# controller6.net
KiCad netlist of a schematic drawn in EAGLE
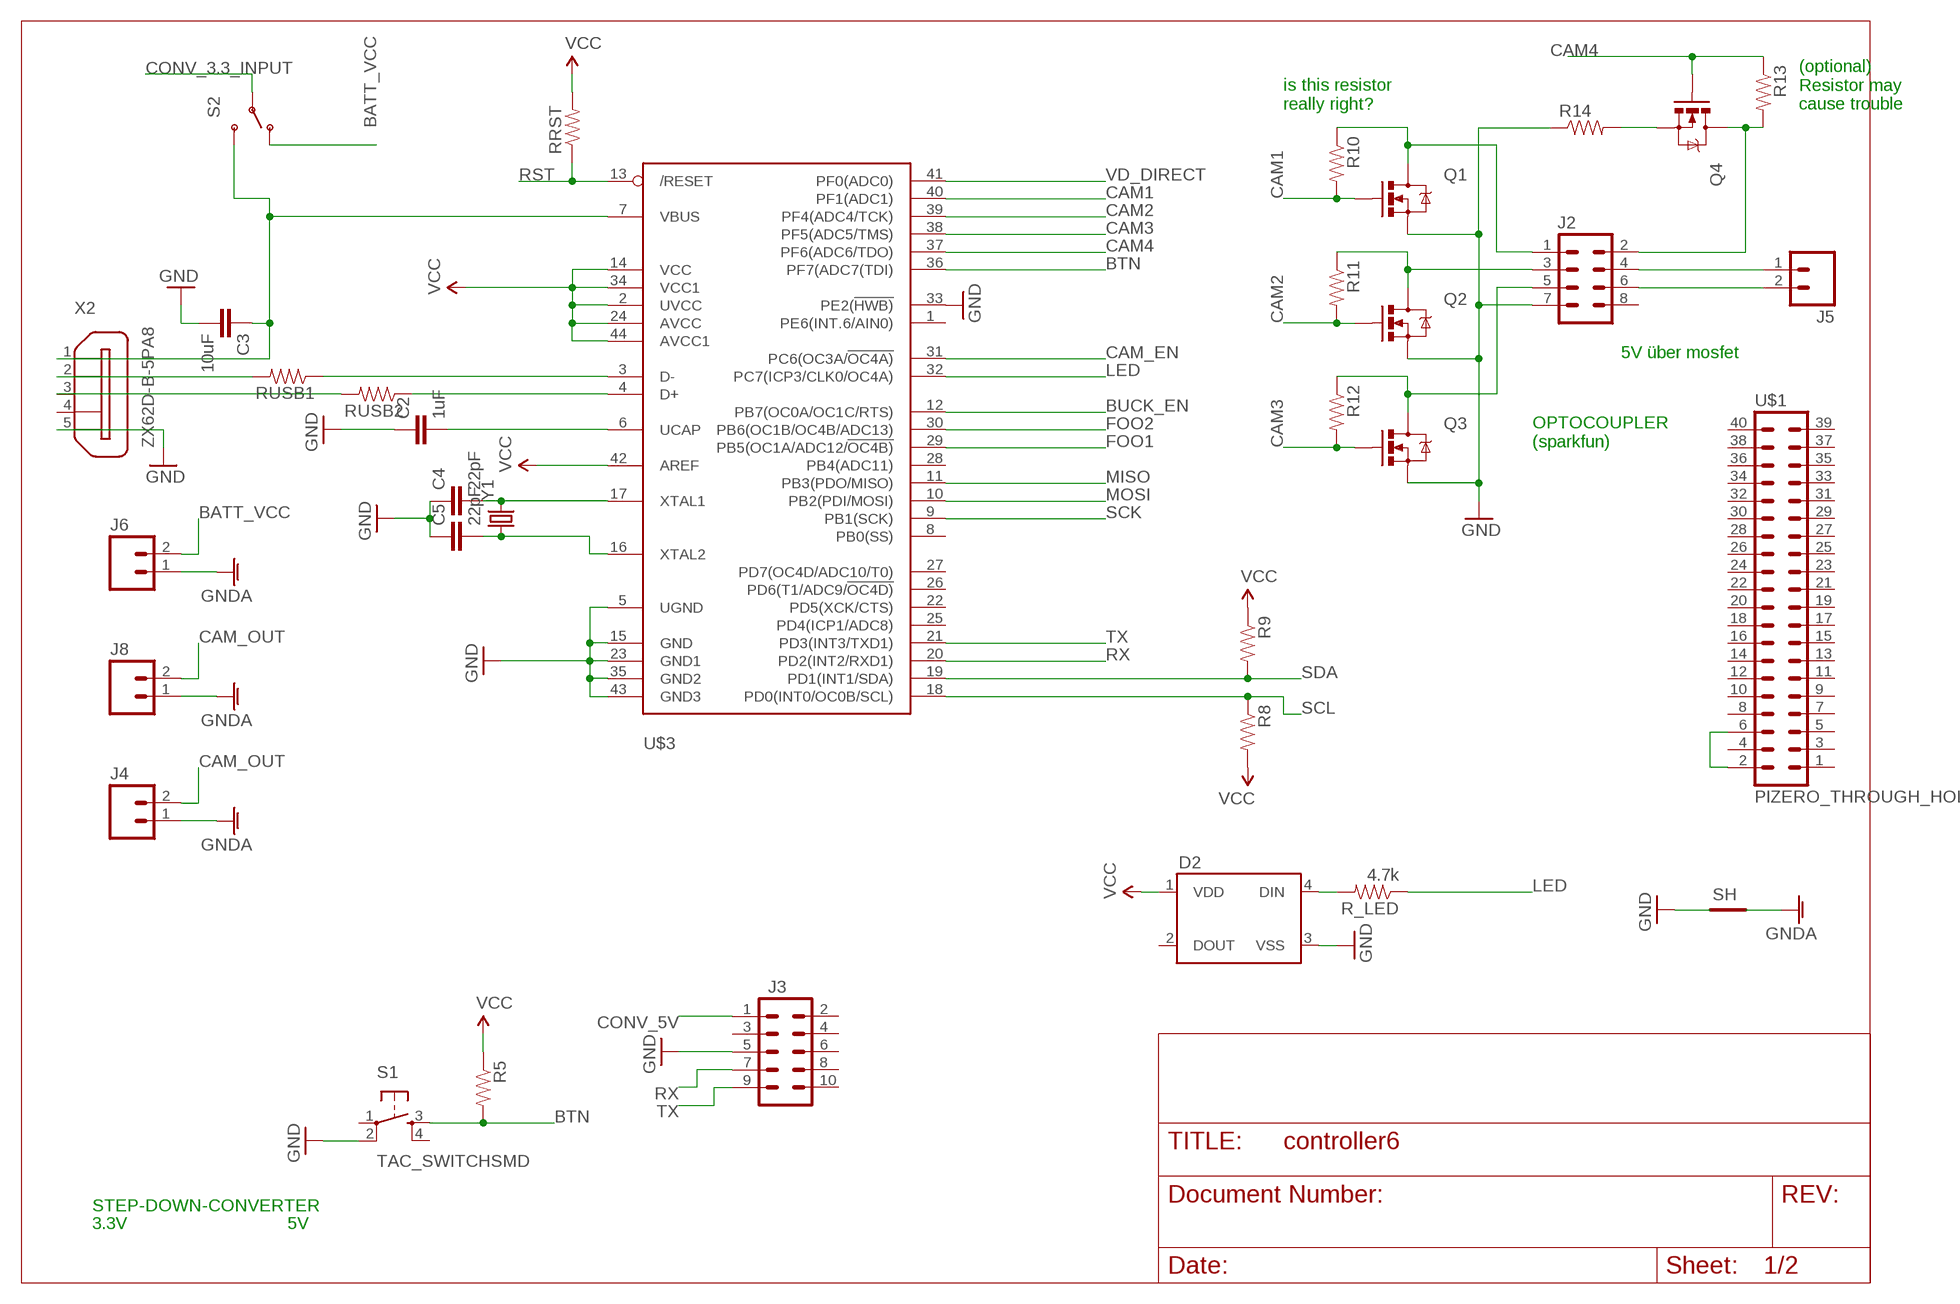
[diagram p0: schematic, sheet 1]
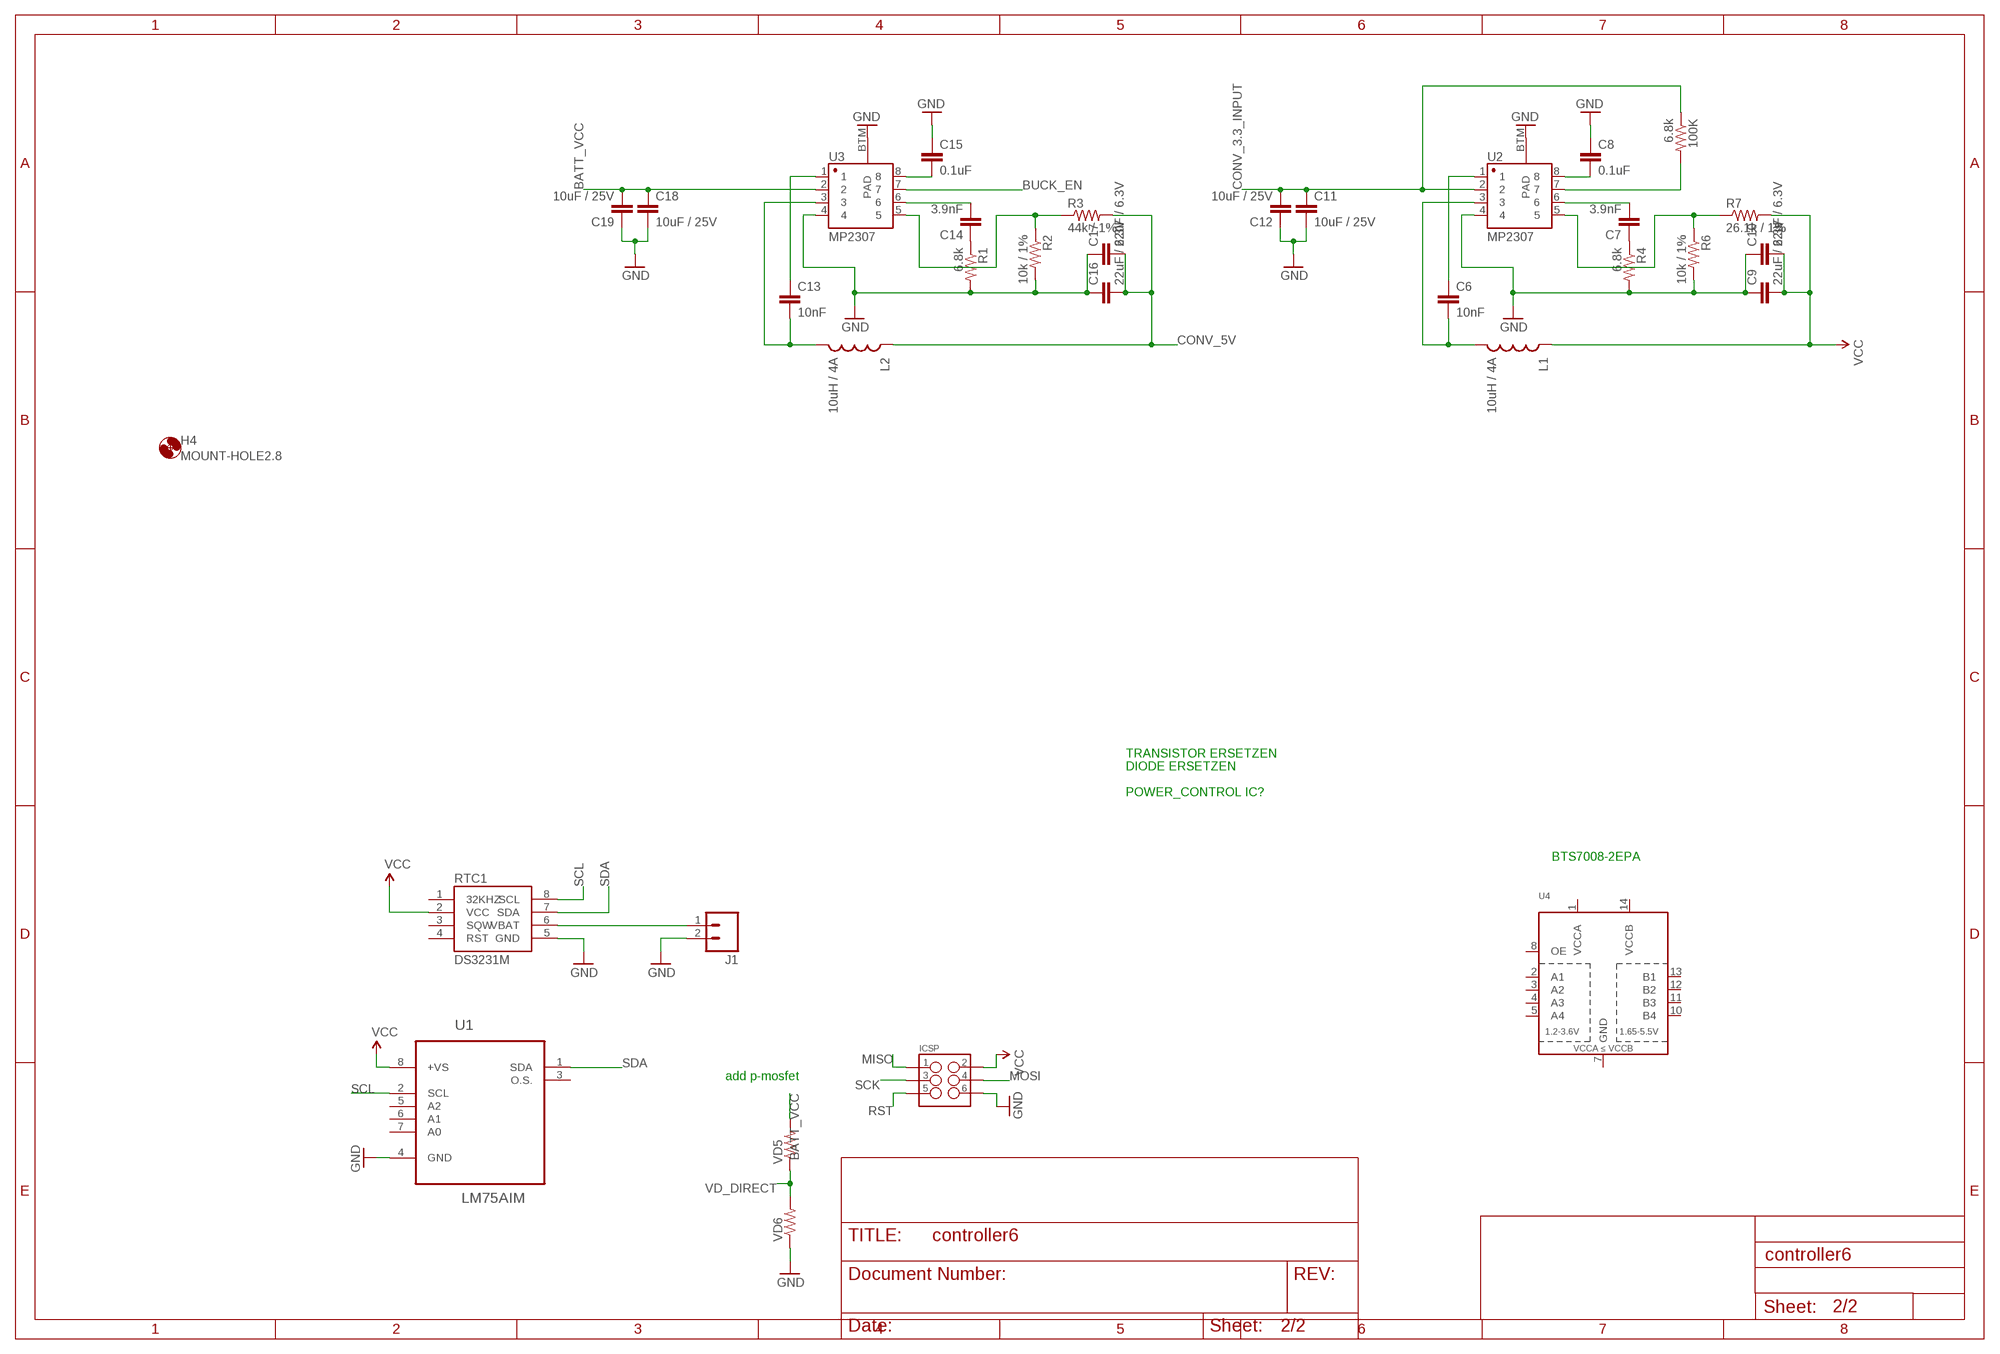
[diagram p1: schematic, sheet 2]

(export (version "E")
  (design (tool "Eeschema 10.0.6"))
  (components
    (comp (ref "100K")
      (value "6.8k")
      (footprint "eagle-import:0805")
      (libsource (lib "eagle-import") (part "SparkFun-Resistors_RESISTOR0805-RES"))
    )
    (comp (ref "C6")
      (value "10nF")
      (footprint "eagle-import:1206")
      (libsource (lib "eagle-import") (part "CAP1206"))
    )
    (comp (ref "C7")
      (value "3.9nF")
      (footprint "eagle-import:0805")
      (libsource (lib "eagle-import") (part "CAP0805"))
    )
    (comp (ref "C8")
      (value "0.1uF")
      (footprint "eagle-import:0805")
      (libsource (lib "eagle-import") (part "CAP0805"))
    )
    (comp (ref "C9")
      (value "22uF / 6.3V")
      (footprint "eagle-import:1206")
      (libsource (lib "eagle-import") (part "CAP1206"))
    )
    (comp (ref "C10")
      (value "22uF / 6.3V")
      (footprint "eagle-import:1206")
      (libsource (lib "eagle-import") (part "CAP1206"))
    )
    (comp (ref "C11")
      (value "10uF / 25V")
      (footprint "eagle-import:1206")
      (libsource (lib "eagle-import") (part "CAP1206"))
    )
    (comp (ref "C12")
      (value "10uF / 25V")
      (footprint "eagle-import:1206")
      (libsource (lib "eagle-import") (part "CAP1206"))
    )
    (comp (ref "C13")
      (value "10nF")
      (footprint "eagle-import:1206")
      (libsource (lib "eagle-import") (part "CAP1206"))
    )
    (comp (ref "C14")
      (value "3.9nF")
      (footprint "eagle-import:0805")
      (libsource (lib "eagle-import") (part "CAP0805"))
    )
    (comp (ref "C15")
      (value "0.1uF")
      (footprint "eagle-import:0805")
      (libsource (lib "eagle-import") (part "CAP0805"))
    )
    (comp (ref "C16")
      (value "22uF / 6.3V")
      (footprint "eagle-import:1206")
      (libsource (lib "eagle-import") (part "CAP1206"))
    )
    (comp (ref "C17")
      (value "22uF / 6.3V")
      (footprint "eagle-import:1206")
      (libsource (lib "eagle-import") (part "CAP1206"))
    )
    (comp (ref "C18")
      (value "10uF / 25V")
      (footprint "eagle-import:1206")
      (libsource (lib "eagle-import") (part "CAP1206"))
    )
    (comp (ref "C19")
      (value "10uF / 25V")
      (footprint "eagle-import:1206")
      (libsource (lib "eagle-import") (part "CAP1206"))
    )
    (comp (ref "H4")
      (value "MOUNT-HOLE2.8")
      (footprint "eagle-import:2,8")
      (libsource (lib "eagle-import") (part "MOUNT-HOLE2.8"))
    )
    (comp (ref "ICSP")
      (value "M03X2FEMALE")
      (footprint "eagle-import:2X3")
      (libsource (lib "eagle-import") (part "M03X2FEMALE"))
    )
    (comp (ref "J1")
      (value "M02LOCK_LONGPADS")
      (footprint "eagle-import:1X02_LOCK_LONGPADS")
      (libsource (lib "eagle-import") (part "M02LOCK_LONGPADS"))
    )
    (comp (ref "L1")
      (value "10uH / 4A")
      (footprint "eagle-import:SDR0403")
      (libsource (lib "eagle-import") (part "INDUCTORSDR0403-560KL"))
    )
    (comp (ref "L2")
      (value "10uH / 4A")
      (footprint "eagle-import:SDR0403")
      (libsource (lib "eagle-import") (part "INDUCTORSDR0403-560KL"))
    )
    (comp (ref "R1")
      (value "6.8k")
      (footprint "eagle-import:0805")
      (libsource (lib "eagle-import") (part "SparkFun-Resistors_RESISTOR0805-RES"))
    )
    (comp (ref "R2")
      (value "10k / 1%")
      (footprint "eagle-import:0805")
      (libsource (lib "eagle-import") (part "SparkFun-Resistors_RESISTOR0805-RES"))
    )
    (comp (ref "R3")
      (value "44k / 1%")
      (footprint "eagle-import:0805")
      (libsource (lib "eagle-import") (part "SparkFun-Resistors_RESISTOR0805-RES"))
    )
    (comp (ref "R4")
      (value "6.8k")
      (footprint "eagle-import:0805")
      (libsource (lib "eagle-import") (part "SparkFun-Resistors_RESISTOR0805-RES"))
    )
    (comp (ref "R6")
      (value "10k / 1%")
      (footprint "eagle-import:0805")
      (libsource (lib "eagle-import") (part "SparkFun-Resistors_RESISTOR0805-RES"))
    )
    (comp (ref "R7")
      (value "26.1k / 1%")
      (footprint "eagle-import:0805")
      (libsource (lib "eagle-import") (part "SparkFun-Resistors_RESISTOR0805-RES"))
    )
    (comp (ref "RTC1")
      (value "DS3231M")
      (footprint "eagle-import:SOIC8")
      (libsource (lib "eagle-import") (part "DS3231M"))
    )
    (comp (ref "U1")
      (value "LM75AIM")
      (footprint "eagle-import:SOIC127P620X175-8N")
      (libsource (lib "eagle-import") (part "LM75AIM"))
    )
    (comp (ref "U2")
      (value "MP2307")
      (footprint "eagle-import:SO08")
      (libsource (lib "eagle-import") (part "GENERIC-SOIC8MSGEQ7N-FILTER"))
    )
    (comp (ref "U3")
      (value "MP2307")
      (footprint "eagle-import:SO08")
      (libsource (lib "eagle-import") (part "GENERIC-SOIC8MSGEQ7N-FILTER"))
    )
    (comp (ref "U4")
      (value "TXB0104PWRSOIC14")
      (footprint "eagle-import:SO14")
      (libsource (lib "eagle-import") (part "TXB0104PWRSOIC14"))
    )
    (comp (ref "VD5")
      (value "RESISTOR1206")
      (footprint "eagle-import:1206")
      (libsource (lib "eagle-import") (part "RESISTOR1206"))
    )
    (comp (ref "VD6")
      (value "RESISTOR1206")
      (footprint "eagle-import:1206")
      (libsource (lib "eagle-import") (part "RESISTOR1206"))
    )
    (comp (ref "C2")
      (value "1uF")
      (footprint "eagle-import:1206")
      (libsource (lib "eagle-import") (part "CAP1206"))
    )
    (comp (ref "C3")
      (value "10uF")
      (footprint "eagle-import:0805")
      (libsource (lib "eagle-import") (part "SparkFun-Passives_CAP0805"))
    )
    (comp (ref "C4")
      (value "22pF")
      (footprint "eagle-import:0805")
      (libsource (lib "eagle-import") (part "SparkFun-Passives_CAP0805"))
    )
    (comp (ref "C5")
      (value "22pF")
      (footprint "eagle-import:0805")
      (libsource (lib "eagle-import") (part "SparkFun-Passives_CAP0805"))
    )
    (comp (ref "D2")
      (value "WS2812B")
      (footprint "eagle-import:WS2812B")
      (libsource (lib "eagle-import") (part "WS2812B"))
    )
    (comp (ref "J2")
      (value "M04X2")
      (footprint "eagle-import:2X4")
      (libsource (lib "eagle-import") (part "M04X2"))
    )
    (comp (ref "J3")
      (value "M05X2NO_SILK")
      (footprint "eagle-import:2X5_NOSILK")
      (libsource (lib "eagle-import") (part "M05X2NO_SILK"))
    )
    (comp (ref "J4")
      (value "M02LOCK")
      (footprint "eagle-import:1X02_LOCK")
      (libsource (lib "eagle-import") (part "M02LOCK"))
    )
    (comp (ref "J5")
      (value "M02PTH")
      (footprint "eagle-import:1X02")
      (libsource (lib "eagle-import") (part "M02PTH"))
    )
    (comp (ref "J6")
      (value "M02LOCK")
      (footprint "eagle-import:1X02_LOCK")
      (libsource (lib "eagle-import") (part "M02LOCK"))
    )
    (comp (ref "J8")
      (value "M02LOCK")
      (footprint "eagle-import:1X02_LOCK")
      (libsource (lib "eagle-import") (part "M02LOCK"))
    )
    (comp (ref "Q1")
      (value "MOSFET-NCHANNELBSS138")
      (footprint "eagle-import:SOT23-3")
      (libsource (lib "eagle-import") (part "MOSFET-NCHANNELBSS138"))
    )
    (comp (ref "Q2")
      (value "MOSFET-NCHANNELBSS138")
      (footprint "eagle-import:SOT23-3")
      (libsource (lib "eagle-import") (part "MOSFET-NCHANNELBSS138"))
    )
    (comp (ref "Q3")
      (value "MOSFET-NCHANNELBSS138")
      (footprint "eagle-import:SOT23-3")
      (libsource (lib "eagle-import") (part "MOSFET-NCHANNELBSS138"))
    )
    (comp (ref "Q4")
      (value "MOSFET-NCHANNELBSS138")
      (footprint "eagle-import:SOT23-3")
      (libsource (lib "eagle-import") (part "MOSFET-NCHANNELBSS138"))
    )
    (comp (ref "R5")
      (value "RESISTOR0805-RES")
      (footprint "eagle-import:0805")
      (libsource (lib "eagle-import") (part "RESISTOR0805-RES"))
    )
    (comp (ref "R8")
      (value "RESISTOR0805-RES")
      (footprint "eagle-import:0805")
      (libsource (lib "eagle-import") (part "RESISTOR0805-RES"))
    )
    (comp (ref "R9")
      (value "RESISTOR0805-RES")
      (footprint "eagle-import:0805")
      (libsource (lib "eagle-import") (part "RESISTOR0805-RES"))
    )
    (comp (ref "R10")
      (value "RESISTOR0805-RES")
      (footprint "eagle-import:0805")
      (libsource (lib "eagle-import") (part "RESISTOR0805-RES"))
    )
    (comp (ref "R11")
      (value "RESISTOR0805-RES")
      (footprint "eagle-import:0805")
      (libsource (lib "eagle-import") (part "RESISTOR0805-RES"))
    )
    (comp (ref "R12")
      (value "RESISTOR0805-RES")
      (footprint "eagle-import:0805")
      (libsource (lib "eagle-import") (part "RESISTOR0805-RES"))
    )
    (comp (ref "R13")
      (value "RESISTOR0805-RES")
      (footprint "eagle-import:0805")
      (libsource (lib "eagle-import") (part "RESISTOR0805-RES"))
    )
    (comp (ref "R14")
      (value "RESISTOR0805-RES")
      (footprint "eagle-import:0805")
      (libsource (lib "eagle-import") (part "RESISTOR0805-RES"))
    )
    (comp (ref "RRST")
      (value "RESISTOR0805-RES")
      (footprint "eagle-import:0805")
      (libsource (lib "eagle-import") (part "RESISTOR0805-RES"))
    )
    (comp (ref "RUSB1")
      (value "RESISTOR0805-RES")
      (footprint "eagle-import:0805")
      (libsource (lib "eagle-import") (part "RESISTOR0805-RES"))
    )
    (comp (ref "RUSB2")
      (value "RESISTOR0805-RES")
      (footprint "eagle-import:0805")
      (libsource (lib "eagle-import") (part "RESISTOR0805-RES"))
    )
    (comp (ref "R_LED")
      (value "4.7k")
      (footprint "eagle-import:0805")
      (libsource (lib "eagle-import") (part "SparkFun-Resistors_RESISTOR0805-RES"))
    )
    (comp (ref "S1")
      (value "TAC_SWITCHSMD")
      (footprint "eagle-import:TACTILE-SWITCH-SMD")
      (libsource (lib "eagle-import") (part "TAC_SWITCHSMD"))
    )
    (comp (ref "S2")
      (value "SWITCH-SPDTPTH_LOCK")
      (footprint "eagle-import:SWITCH-SPDT_LOCK.007S")
      (libsource (lib "eagle-import") (part "SWITCH-SPDTPTH_LOCK"))
    )
    (comp (ref "SH")
      (value "SHORT-HT5")
      (footprint "eagle-import:SHORT_TOP-50")
      (libsource (lib "eagle-import") (part "SHORT-HT5"))
    )
    (comp (ref "U$1")
      (value "PIZERO_THROUGH_HOLE")
      (footprint "eagle-import:PIZERO_THOUGH_HOLE")
      (libsource (lib "eagle-import") (part "PIZERO_THROUGH_HOLE"))
    )
    (comp (ref "U$3")
      (value "ATMEGA32U4-AU")
      (footprint "eagle-import:TQFP44")
      (libsource (lib "eagle-import") (part "ATMEGA32U4-AU"))
    )
    (comp (ref "X2")
      (value "ZX62D-B-5PA8")
      (footprint "eagle-import:ZX62D-B-5PA8")
      (fields (field (name "MF") "Hirose"))
      (libsource (lib "eagle-import") (part "ZX62D-B-5PA8"))
    )
    (comp (ref "Y1")
      (value "CRYSTALCRYSTAL-SMD-5X3-16MHZ")
      (footprint "eagle-import:CRYSTAL-SMD-5X3")
      (libsource (lib "eagle-import") (part "CRYSTALCRYSTAL-SMD-5X3-16MHZ"))
    )
  )
  (nets
    (net (code "1") (name "BATT_VCC") (class "Default")
      (node (ref "C18") (pin "1") (pinfunction "1_1") (pintype "passive"))
      (node (ref "C19") (pin "2") (pinfunction "2_2") (pintype "passive"))
      (node (ref "J6") (pin "2") (pinfunction "2_2") (pintype "passive"))
      (node (ref "S2") (pin "1") (pinfunction "O_1") (pintype "passive"))
      (node (ref "U3") (pin "2") (pinfunction "2_2") (pintype "bidirectional"))
      (node (ref "VD5") (pin "2") (pinfunction "2_2") (pintype "passive"))
    )
    (net (code "2") (name "BTN") (class "Default")
      (node (ref "R5") (pin "2") (pinfunction "2_2") (pintype "passive"))
      (node (ref "S1") (pin "3") (pinfunction "3_3") (pintype "passive"))
      (node (ref "U$3") (pin "36") (pinfunction "PF7(ADC7(TDI)_36") (pintype "bidirectional"))
    )
    (net (code "3") (name "BUCK_EN") (class "Default")
      (node (ref "U$3") (pin "12") (pinfunction "PB7(OC0A/OC1C/RTS)_12") (pintype "bidirectional"))
      (node (ref "U3") (pin "7") (pinfunction "7_7") (pintype "bidirectional"))
    )
    (net (code "4") (name "CAM1") (class "Default")
      (node (ref "Q1") (pin "1") (pinfunction "G_1") (pintype "passive"))
      (node (ref "R10") (pin "2") (pinfunction "2_2") (pintype "passive"))
      (node (ref "U$3") (pin "40") (pinfunction "PF1(ADC1)_40") (pintype "bidirectional"))
    )
    (net (code "5") (name "CAM2") (class "Default")
      (node (ref "Q2") (pin "1") (pinfunction "G_1") (pintype "passive"))
      (node (ref "R11") (pin "2") (pinfunction "2_2") (pintype "passive"))
      (node (ref "U$3") (pin "39") (pinfunction "PF4(ADC4/TCK)_39") (pintype "bidirectional"))
    )
    (net (code "6") (name "CAM3") (class "Default")
      (node (ref "Q3") (pin "1") (pinfunction "G_1") (pintype "passive"))
      (node (ref "R12") (pin "2") (pinfunction "2_2") (pintype "passive"))
      (node (ref "U$3") (pin "38") (pinfunction "PF5(ADC5/TMS)_38") (pintype "bidirectional"))
    )
    (net (code "7") (name "CAM4") (class "Default")
      (node (ref "Q4") (pin "1") (pinfunction "G_1") (pintype "passive"))
      (node (ref "R13") (pin "1") (pinfunction "1_1") (pintype "passive"))
      (node (ref "U$3") (pin "37") (pinfunction "PF6(ADC6/TDO)_37") (pintype "bidirectional"))
    )
    (net (code "8") (name "CAM_EN") (class "Default")
      (node (ref "U$3") (pin "31") (pinfunction "PC6(OC3A/~{OC4A})_31") (pintype "bidirectional"))
    )
    (net (code "9") (name "CAM_OUT") (class "Default")
      (node (ref "J4") (pin "2") (pinfunction "2_2") (pintype "passive"))
      (node (ref "J8") (pin "2") (pinfunction "2_2") (pintype "passive"))
    )
    (net (code "10") (name "CONV_3.3_INPUT") (class "Default")
      (node (ref "100K") (pin "1") (pinfunction "1_1") (pintype "passive"))
      (node (ref "C11") (pin "1") (pinfunction "1_1") (pintype "passive"))
      (node (ref "C12") (pin "2") (pinfunction "2_2") (pintype "passive"))
      (node (ref "S2") (pin "2") (pinfunction "P_2") (pintype "passive"))
      (node (ref "U2") (pin "2") (pinfunction "2_2") (pintype "bidirectional"))
    )
    (net (code "11") (name "CONV_5V") (class "Default")
      (node (ref "C16") (pin "2") (pinfunction "2_2") (pintype "passive"))
      (node (ref "C17") (pin "2") (pinfunction "2_2") (pintype "passive"))
      (node (ref "J3") (pin "1") (pinfunction "1_1") (pintype "passive"))
      (node (ref "L2") (pin "P$1") (pinfunction "1_P$1") (pintype "passive"))
      (node (ref "R3") (pin "2") (pinfunction "2_2") (pintype "passive"))
    )
    (net (code "12") (name "FOO1") (class "Default")
      (node (ref "U$3") (pin "29") (pinfunction "PB5(OC1A/ADC12/~{OC4B})_29") (pintype "bidirectional"))
    )
    (net (code "13") (name "FOO2") (class "Default")
      (node (ref "U$3") (pin "30") (pinfunction "PB6(OC1B/OC4B/ADC13)_30") (pintype "bidirectional"))
    )
    (net (code "14") (name "GND") (class "Default")
      (node (ref "C10") (pin "1") (pinfunction "1_1") (pintype "passive"))
      (node (ref "C11") (pin "2") (pinfunction "2_2") (pintype "passive"))
      (node (ref "C12") (pin "1") (pinfunction "1_1") (pintype "passive"))
      (node (ref "C15") (pin "1") (pinfunction "1_1") (pintype "passive"))
      (node (ref "C16") (pin "1") (pinfunction "1_1") (pintype "passive"))
      (node (ref "C17") (pin "1") (pinfunction "1_1") (pintype "passive"))
      (node (ref "C18") (pin "2") (pinfunction "2_2") (pintype "passive"))
      (node (ref "C19") (pin "1") (pinfunction "1_1") (pintype "passive"))
      (node (ref "C2") (pin "1") (pinfunction "1_1") (pintype "passive"))
      (node (ref "C3") (pin "2") (pinfunction "2_2") (pintype "passive"))
      (node (ref "C4") (pin "1") (pinfunction "1_1") (pintype "passive"))
      (node (ref "C5") (pin "1") (pinfunction "1_1") (pintype "passive"))
      (node (ref "C8") (pin "1") (pinfunction "1_1") (pintype "passive"))
      (node (ref "C9") (pin "1") (pinfunction "1_1") (pintype "passive"))
      (node (ref "D2") (pin "3") (pinfunction "VSS_3") (pintype "power_in"))
      (node (ref "ICSP") (pin "6") (pinfunction "6_6") (pintype "bidirectional"))
      (node (ref "J1") (pin "2") (pinfunction "2_2") (pintype "passive"))
      (node (ref "J2") (pin "7") (pinfunction "7_7") (pintype "passive"))
      (node (ref "J3") (pin "5") (pinfunction "5_5") (pintype "passive"))
      (node (ref "Q1") (pin "2") (pinfunction "S_2") (pintype "passive"))
      (node (ref "Q2") (pin "2") (pinfunction "S_2") (pintype "passive"))
      (node (ref "Q3") (pin "2") (pinfunction "S_2") (pintype "passive"))
      (node (ref "R1") (pin "2") (pinfunction "2_2") (pintype "passive"))
      (node (ref "R14") (pin "1") (pinfunction "1_1") (pintype "passive"))
      (node (ref "R2") (pin "2") (pinfunction "2_2") (pintype "passive"))
      (node (ref "R4") (pin "2") (pinfunction "2_2") (pintype "passive"))
      (node (ref "R6") (pin "2") (pinfunction "2_2") (pintype "passive"))
      (node (ref "RTC1") (pin "5") (pinfunction "GND_5") (pintype "power_in"))
      (node (ref "S1") (pin "2") (pinfunction "2_2") (pintype "passive"))
      (node (ref "SH") (pin "1") (pinfunction "P$1_1") (pintype "bidirectional"))
      (node (ref "U$3") (pin "15") (pinfunction "GND_15") (pintype "bidirectional"))
      (node (ref "U$3") (pin "23") (pinfunction "GND1_23") (pintype "bidirectional"))
      (node (ref "U$3") (pin "33") (pinfunction "PE2(~{HWB})_33") (pintype "bidirectional"))
      (node (ref "U$3") (pin "35") (pinfunction "GND2_35") (pintype "bidirectional"))
      (node (ref "U$3") (pin "43") (pinfunction "GND3_43") (pintype "bidirectional"))
      (node (ref "U$3") (pin "5") (pinfunction "UGND_5") (pintype "bidirectional"))
      (node (ref "U1") (pin "4") (pinfunction "GND_4") (pintype "passive"))
      (node (ref "U2") (pin "4") (pinfunction "4_4") (pintype "bidirectional"))
      (node (ref "U2") (pin "BTM") (pinfunction "PAD_BTM") (pintype "bidirectional"))
      (node (ref "U3") (pin "4") (pinfunction "4_4") (pintype "bidirectional"))
      (node (ref "U3") (pin "BTM") (pinfunction "PAD_BTM") (pintype "bidirectional"))
      (node (ref "VD6") (pin "1") (pinfunction "1_1") (pintype "passive"))
      (node (ref "X2") (pin "5") (pinfunction "5_5") (pintype "passive"))
    )
    (net (code "15") (name "GNDA") (class "Default")
      (node (ref "J4") (pin "1") (pinfunction "1_1") (pintype "passive"))
      (node (ref "J6") (pin "1") (pinfunction "1_1") (pintype "passive"))
      (node (ref "J8") (pin "1") (pinfunction "1_1") (pintype "passive"))
      (node (ref "SH") (pin "2") (pinfunction "P$2_2") (pintype "bidirectional"))
    )
    (net (code "16") (name "LED") (class "Default")
      (node (ref "R_LED") (pin "1") (pinfunction "1_1") (pintype "passive"))
      (node (ref "U$3") (pin "32") (pinfunction "PC7(ICP3/CLK0/OC4A)_32") (pintype "bidirectional"))
    )
    (net (code "17") (name "MISO") (class "Default")
      (node (ref "ICSP") (pin "1") (pinfunction "1_1") (pintype "bidirectional"))
      (node (ref "U$3") (pin "11") (pinfunction "PB3(PDO/MISO)_11") (pintype "bidirectional"))
    )
    (net (code "18") (name "MOSI") (class "Default")
      (node (ref "ICSP") (pin "4") (pinfunction "4_4") (pintype "bidirectional"))
      (node (ref "U$3") (pin "10") (pinfunction "PB2(PDI/MOSI)_10") (pintype "bidirectional"))
    )
    (net (code "19") (name "Net-(100K-Pad2)") (class "Default")
      (node (ref "100K") (pin "2") (pinfunction "2_2") (pintype "passive"))
      (node (ref "U2") (pin "7") (pinfunction "7_7") (pintype "bidirectional"))
    )
    (net (code "20") (name "Net-(C6-Pad1)") (class "Default")
      (node (ref "C6") (pin "1") (pinfunction "1_1") (pintype "passive"))
      (node (ref "U2") (pin "1") (pinfunction "1_1") (pintype "bidirectional"))
    )
    (net (code "21") (name "Net-(C7-Pad1)") (class "Default")
      (node (ref "C7") (pin "1") (pinfunction "1_1") (pintype "passive"))
      (node (ref "R4") (pin "1") (pinfunction "1_1") (pintype "passive"))
    )
    (net (code "22") (name "Net-(C7-Pad2)") (class "Default")
      (node (ref "C7") (pin "2") (pinfunction "2_2") (pintype "passive"))
      (node (ref "U2") (pin "6") (pinfunction "6_6") (pintype "bidirectional"))
    )
    (net (code "23") (name "Net-(C8-Pad2)") (class "Default")
      (node (ref "C8") (pin "2") (pinfunction "2_2") (pintype "passive"))
      (node (ref "U2") (pin "8") (pinfunction "8_8") (pintype "bidirectional"))
    )
    (net (code "24") (name "Net-(C13-Pad1)") (class "Default")
      (node (ref "C13") (pin "1") (pinfunction "1_1") (pintype "passive"))
      (node (ref "U3") (pin "1") (pinfunction "1_1") (pintype "bidirectional"))
    )
    (net (code "25") (name "Net-(C14-Pad1)") (class "Default")
      (node (ref "C14") (pin "1") (pinfunction "1_1") (pintype "passive"))
      (node (ref "R1") (pin "1") (pinfunction "1_1") (pintype "passive"))
    )
    (net (code "26") (name "Net-(C14-Pad2)") (class "Default")
      (node (ref "C14") (pin "2") (pinfunction "2_2") (pintype "passive"))
      (node (ref "U3") (pin "6") (pinfunction "6_6") (pintype "bidirectional"))
    )
    (net (code "27") (name "Net-(C15-Pad2)") (class "Default")
      (node (ref "C15") (pin "2") (pinfunction "2_2") (pintype "passive"))
      (node (ref "U3") (pin "8") (pinfunction "8_8") (pintype "bidirectional"))
    )
    (net (code "28") (name "Net-(D2-DIN)") (class "Default")
      (node (ref "D2") (pin "4") (pinfunction "DIN_4") (pintype "input"))
      (node (ref "R_LED") (pin "2") (pinfunction "2_2") (pintype "passive"))
    )
    (net (code "29") (name "Net-(J2-Pad4)") (class "Default")
      (node (ref "J2") (pin "4") (pinfunction "4_4") (pintype "passive"))
      (node (ref "J5") (pin "1") (pinfunction "1_1") (pintype "passive"))
    )
    (net (code "30") (name "Net-(J2-Pad6)") (class "Default")
      (node (ref "J2") (pin "6") (pinfunction "6_6") (pintype "passive"))
      (node (ref "J5") (pin "2") (pinfunction "2_2") (pintype "passive"))
    )
    (net (code "31") (name "Net-(L1-2)") (class "Default")
      (node (ref "C6") (pin "2") (pinfunction "2_2") (pintype "passive"))
      (node (ref "L1") (pin "P$2") (pinfunction "2_P$2") (pintype "passive"))
      (node (ref "U2") (pin "3") (pinfunction "3_3") (pintype "bidirectional"))
    )
    (net (code "32") (name "Net-(L2-2)") (class "Default")
      (node (ref "C13") (pin "2") (pinfunction "2_2") (pintype "passive"))
      (node (ref "L2") (pin "P$2") (pinfunction "2_P$2") (pintype "passive"))
      (node (ref "U3") (pin "3") (pinfunction "3_3") (pintype "bidirectional"))
    )
    (net (code "33") (name "Net-(Q1-D)") (class "Default")
      (node (ref "J2") (pin "1") (pinfunction "1_1") (pintype "passive"))
      (node (ref "Q1") (pin "3") (pinfunction "D_3") (pintype "passive"))
      (node (ref "R10") (pin "1") (pinfunction "1_1") (pintype "passive"))
    )
    (net (code "34") (name "Net-(Q2-D)") (class "Default")
      (node (ref "J2") (pin "3") (pinfunction "3_3") (pintype "passive"))
      (node (ref "Q2") (pin "3") (pinfunction "D_3") (pintype "passive"))
      (node (ref "R11") (pin "1") (pinfunction "1_1") (pintype "passive"))
    )
    (net (code "35") (name "Net-(Q3-D)") (class "Default")
      (node (ref "J2") (pin "5") (pinfunction "5_5") (pintype "passive"))
      (node (ref "Q3") (pin "3") (pinfunction "D_3") (pintype "passive"))
      (node (ref "R12") (pin "1") (pinfunction "1_1") (pintype "passive"))
    )
    (net (code "36") (name "Net-(Q4-D)") (class "Default")
      (node (ref "J2") (pin "2") (pinfunction "2_2") (pintype "passive"))
      (node (ref "Q4") (pin "3") (pinfunction "D_3") (pintype "passive"))
      (node (ref "R13") (pin "2") (pinfunction "2_2") (pintype "passive"))
    )
    (net (code "37") (name "Net-(Q4-S)") (class "Default")
      (node (ref "Q4") (pin "2") (pinfunction "S_2") (pintype "passive"))
      (node (ref "R14") (pin "2") (pinfunction "2_2") (pintype "passive"))
    )
    (net (code "38") (name "Net-(R2-Pad1)") (class "Default")
      (node (ref "R2") (pin "1") (pinfunction "1_1") (pintype "passive"))
      (node (ref "R3") (pin "1") (pinfunction "1_1") (pintype "passive"))
      (node (ref "U3") (pin "5") (pinfunction "5_5") (pintype "bidirectional"))
    )
    (net (code "39") (name "Net-(R6-Pad1)") (class "Default")
      (node (ref "R6") (pin "1") (pinfunction "1_1") (pintype "passive"))
      (node (ref "R7") (pin "1") (pinfunction "1_1") (pintype "passive"))
      (node (ref "U2") (pin "5") (pinfunction "5_5") (pintype "bidirectional"))
    )
    (net (code "40") (name "Net-(RTC1-VBAT)") (class "Default")
      (node (ref "J1") (pin "1") (pinfunction "1_1") (pintype "passive"))
      (node (ref "RTC1") (pin "6") (pinfunction "VBAT_6") (pintype "power_in"))
    )
    (net (code "41") (name "Net-(RUSB1-Pad2)") (class "Default")
      (node (ref "RUSB1") (pin "2") (pinfunction "2_2") (pintype "passive"))
      (node (ref "X2") (pin "2") (pinfunction "2_2") (pintype "passive"))
    )
    (net (code "42") (name "Net-(RUSB2-Pad2)") (class "Default")
      (node (ref "RUSB2") (pin "2") (pinfunction "2_2") (pintype "passive"))
      (node (ref "X2") (pin "3") (pinfunction "3_3") (pintype "passive"))
    )
    (net (code "43") (name "Net-(S2-S)") (class "Default")
      (node (ref "C3") (pin "1") (pinfunction "1_1") (pintype "passive"))
      (node (ref "S2") (pin "3") (pinfunction "S_3") (pintype "passive"))
      (node (ref "U$3") (pin "7") (pinfunction "VBUS_7") (pintype "bidirectional"))
      (node (ref "X2") (pin "1") (pinfunction "1_1") (pintype "passive"))
    )
    (net (code "44") (name "Net-(U$1-Pad2)") (class "Default")
      (node (ref "U$1") (pin "2") (pinfunction "2_2") (pintype "passive"))
      (node (ref "U$1") (pin "6") (pinfunction "6_6") (pintype "passive"))
    )
    (net (code "45") (name "Net-(U$3-D+)") (class "Default")
      (node (ref "RUSB2") (pin "1") (pinfunction "1_1") (pintype "passive"))
      (node (ref "U$3") (pin "4") (pinfunction "D+_4") (pintype "bidirectional"))
    )
    (net (code "46") (name "Net-(U$3-D-)") (class "Default")
      (node (ref "RUSB1") (pin "1") (pinfunction "1_1") (pintype "passive"))
      (node (ref "U$3") (pin "3") (pinfunction "D-_3") (pintype "bidirectional"))
    )
    (net (code "47") (name "Net-(U$3-UCAP)") (class "Default")
      (node (ref "C2") (pin "2") (pinfunction "2_2") (pintype "passive"))
      (node (ref "U$3") (pin "6") (pinfunction "UCAP_6") (pintype "bidirectional"))
    )
    (net (code "48") (name "Net-(U$3-XTAL1)") (class "Default")
      (node (ref "C4") (pin "2") (pinfunction "2_2") (pintype "passive"))
      (node (ref "U$3") (pin "17") (pinfunction "XTAL1_17") (pintype "bidirectional"))
      (node (ref "Y1") (pin "3") (pinfunction "2_3") (pintype "passive"))
    )
    (net (code "49") (name "Net-(U$3-XTAL2)") (class "Default")
      (node (ref "C5") (pin "2") (pinfunction "2_2") (pintype "passive"))
      (node (ref "U$3") (pin "16") (pinfunction "XTAL2_16") (pintype "bidirectional"))
      (node (ref "Y1") (pin "1") (pinfunction "1_1") (pintype "passive"))
    )
    (net (code "50") (name "RST") (class "Default")
      (node (ref "ICSP") (pin "5") (pinfunction "5_5") (pintype "bidirectional"))
      (node (ref "RRST") (pin "1") (pinfunction "1_1") (pintype "passive"))
      (node (ref "U$3") (pin "13") (pinfunction "/RESET_13") (pintype "bidirectional"))
    )
    (net (code "51") (name "RX") (class "Default")
      (node (ref "J3") (pin "7") (pinfunction "7_7") (pintype "passive"))
      (node (ref "U$3") (pin "20") (pinfunction "PD2(INT2/RXD1)_20") (pintype "bidirectional"))
    )
    (net (code "52") (name "SCK") (class "Default")
      (node (ref "ICSP") (pin "3") (pinfunction "3_3") (pintype "bidirectional"))
      (node (ref "U$3") (pin "9") (pinfunction "PB1(SCK)_9") (pintype "bidirectional"))
    )
    (net (code "53") (name "SCL") (class "Default")
      (node (ref "R8") (pin "1") (pinfunction "1_1") (pintype "passive"))
      (node (ref "RTC1") (pin "8") (pinfunction "SCL_8") (pintype "bidirectional"))
      (node (ref "U$3") (pin "18") (pinfunction "PD0(INT0/OC0B/SCL)_18") (pintype "bidirectional"))
      (node (ref "U1") (pin "2") (pinfunction "SCL_2") (pintype "input"))
    )
    (net (code "54") (name "SDA") (class "Default")
      (node (ref "R9") (pin "2") (pinfunction "2_2") (pintype "passive"))
      (node (ref "RTC1") (pin "7") (pinfunction "SDA_7") (pintype "bidirectional"))
      (node (ref "U$3") (pin "19") (pinfunction "PD1(INT1/SDA)_19") (pintype "bidirectional"))
      (node (ref "U1") (pin "1") (pinfunction "SDA_1") (pintype "bidirectional"))
    )
    (net (code "55") (name "TX") (class "Default")
      (node (ref "J3") (pin "9") (pinfunction "9_9") (pintype "passive"))
      (node (ref "U$3") (pin "21") (pinfunction "PD3(INT3/TXD1)_21") (pintype "bidirectional"))
    )
    (net (code "56") (name "VCC") (class "Default")
      (node (ref "C10") (pin "2") (pinfunction "2_2") (pintype "passive"))
      (node (ref "C9") (pin "2") (pinfunction "2_2") (pintype "passive"))
      (node (ref "D2") (pin "1") (pinfunction "VDD_1") (pintype "power_in"))
      (node (ref "ICSP") (pin "2") (pinfunction "2_2") (pintype "bidirectional"))
      (node (ref "L1") (pin "P$1") (pinfunction "1_P$1") (pintype "passive"))
      (node (ref "R5") (pin "1") (pinfunction "1_1") (pintype "passive"))
      (node (ref "R7") (pin "2") (pinfunction "2_2") (pintype "passive"))
      (node (ref "R8") (pin "2") (pinfunction "2_2") (pintype "passive"))
      (node (ref "R9") (pin "1") (pinfunction "1_1") (pintype "passive"))
      (node (ref "RRST") (pin "2") (pinfunction "2_2") (pintype "passive"))
      (node (ref "RTC1") (pin "2") (pinfunction "VCC_2") (pintype "power_in"))
      (node (ref "U$3") (pin "14") (pinfunction "VCC_14") (pintype "bidirectional"))
      (node (ref "U$3") (pin "2") (pinfunction "UVCC_2") (pintype "bidirectional"))
      (node (ref "U$3") (pin "24") (pinfunction "AVCC_24") (pintype "bidirectional"))
      (node (ref "U$3") (pin "34") (pinfunction "VCC1_34") (pintype "bidirectional"))
      (node (ref "U$3") (pin "42") (pinfunction "AREF_42") (pintype "bidirectional"))
      (node (ref "U$3") (pin "44") (pinfunction "AVCC1_44") (pintype "bidirectional"))
      (node (ref "U1") (pin "8") (pinfunction "+VS_8") (pintype "power_in"))
    )
    (net (code "57") (name "VD_DIRECT") (class "Default")
      (node (ref "U$3") (pin "41") (pinfunction "PF0(ADC0)_41") (pintype "bidirectional"))
      (node (ref "VD5") (pin "1") (pinfunction "1_1") (pintype "passive"))
      (node (ref "VD6") (pin "2") (pinfunction "2_2") (pintype "passive"))
    )
    (net (code "58") (name "unconnected-(D2-DOUT-Pad2)") (class "Default")
      (node (ref "D2") (pin "2") (pinfunction "DOUT_2") (pintype "output"))
    )
    (net (code "59") (name "unconnected-(J2-Pad8)") (class "Default")
      (node (ref "J2") (pin "8") (pinfunction "8_8") (pintype "passive"))
    )
    (net (code "60") (name "unconnected-(J3-Pad2)") (class "Default")
      (node (ref "J3") (pin "2") (pinfunction "2_2") (pintype "passive"))
    )
    (net (code "61") (name "unconnected-(J3-Pad3)") (class "Default")
      (node (ref "J3") (pin "3") (pinfunction "3_3") (pintype "passive"))
    )
    (net (code "62") (name "unconnected-(J3-Pad4)") (class "Default")
      (node (ref "J3") (pin "4") (pinfunction "4_4") (pintype "passive"))
    )
    (net (code "63") (name "unconnected-(J3-Pad6)") (class "Default")
      (node (ref "J3") (pin "6") (pinfunction "6_6") (pintype "passive"))
    )
    (net (code "64") (name "unconnected-(J3-Pad8)") (class "Default")
      (node (ref "J3") (pin "8") (pinfunction "8_8") (pintype "passive"))
    )
    (net (code "65") (name "unconnected-(J3-Pad10)") (class "Default")
      (node (ref "J3") (pin "10") (pinfunction "10_10") (pintype "passive"))
    )
    (net (code "66") (name "unconnected-(RTC1-32KHZ-Pad1)") (class "Default")
      (node (ref "RTC1") (pin "1") (pinfunction "32KHZ_1") (pintype "output"))
    )
    (net (code "67") (name "unconnected-(RTC1-RST-Pad4)") (class "Default")
      (node (ref "RTC1") (pin "4") (pinfunction "RST_4") (pintype "bidirectional"))
    )
    (net (code "68") (name "unconnected-(RTC1-SQW-Pad3)") (class "Default")
      (node (ref "RTC1") (pin "3") (pinfunction "SQW_3") (pintype "output"))
    )
    (net (code "69") (name "unconnected-(S1-Pad1)") (class "Default")
      (node (ref "S1") (pin "1") (pinfunction "1_1") (pintype "passive"))
    )
    (net (code "70") (name "unconnected-(S1-Pad4)") (class "Default")
      (node (ref "S1") (pin "4") (pinfunction "4_4") (pintype "passive"))
    )
    (net (code "71") (name "unconnected-(U$1-Pad1)") (class "Default")
      (node (ref "U$1") (pin "1") (pinfunction "1_1") (pintype "passive"))
    )
    (net (code "72") (name "unconnected-(U$1-Pad3)") (class "Default")
      (node (ref "U$1") (pin "3") (pinfunction "3_3") (pintype "passive"))
    )
    (net (code "73") (name "unconnected-(U$1-Pad4)") (class "Default")
      (node (ref "U$1") (pin "4") (pinfunction "4_4") (pintype "passive"))
    )
    (net (code "74") (name "unconnected-(U$1-Pad5)") (class "Default")
      (node (ref "U$1") (pin "5") (pinfunction "5_5") (pintype "passive"))
    )
    (net (code "75") (name "unconnected-(U$1-Pad7)") (class "Default")
      (node (ref "U$1") (pin "7") (pinfunction "7_7") (pintype "passive"))
    )
    (net (code "76") (name "unconnected-(U$1-Pad8)") (class "Default")
      (node (ref "U$1") (pin "8") (pinfunction "8_8") (pintype "passive"))
    )
    (net (code "77") (name "unconnected-(U$1-Pad9)") (class "Default")
      (node (ref "U$1") (pin "9") (pinfunction "9_9") (pintype "passive"))
    )
    (net (code "78") (name "unconnected-(U$1-Pad10)") (class "Default")
      (node (ref "U$1") (pin "10") (pinfunction "10_10") (pintype "passive"))
    )
    (net (code "79") (name "unconnected-(U$1-Pad11)") (class "Default")
      (node (ref "U$1") (pin "11") (pinfunction "11_11") (pintype "passive"))
    )
    (net (code "80") (name "unconnected-(U$1-Pad12)") (class "Default")
      (node (ref "U$1") (pin "12") (pinfunction "12_12") (pintype "passive"))
    )
    (net (code "81") (name "unconnected-(U$1-Pad13)") (class "Default")
      (node (ref "U$1") (pin "13") (pinfunction "13_13") (pintype "passive"))
    )
    (net (code "82") (name "unconnected-(U$1-Pad14)") (class "Default")
      (node (ref "U$1") (pin "14") (pinfunction "14_14") (pintype "passive"))
    )
    (net (code "83") (name "unconnected-(U$1-Pad15)") (class "Default")
      (node (ref "U$1") (pin "15") (pinfunction "15_15") (pintype "passive"))
    )
    (net (code "84") (name "unconnected-(U$1-Pad16)") (class "Default")
      (node (ref "U$1") (pin "16") (pinfunction "16_16") (pintype "passive"))
    )
    (net (code "85") (name "unconnected-(U$1-Pad17)") (class "Default")
      (node (ref "U$1") (pin "17") (pinfunction "17_17") (pintype "passive"))
    )
    (net (code "86") (name "unconnected-(U$1-Pad18)") (class "Default")
      (node (ref "U$1") (pin "18") (pinfunction "18_18") (pintype "passive"))
    )
    (net (code "87") (name "unconnected-(U$1-Pad19)") (class "Default")
      (node (ref "U$1") (pin "19") (pinfunction "19_19") (pintype "passive"))
    )
    (net (code "88") (name "unconnected-(U$1-Pad20)") (class "Default")
      (node (ref "U$1") (pin "20") (pinfunction "20_20") (pintype "passive"))
    )
    (net (code "89") (name "unconnected-(U$1-Pad21)") (class "Default")
      (node (ref "U$1") (pin "21") (pinfunction "21_21") (pintype "passive"))
    )
    (net (code "90") (name "unconnected-(U$1-Pad22)") (class "Default")
      (node (ref "U$1") (pin "22") (pinfunction "22_22") (pintype "passive"))
    )
    (net (code "91") (name "unconnected-(U$1-Pad23)") (class "Default")
      (node (ref "U$1") (pin "23") (pinfunction "23_23") (pintype "passive"))
    )
    (net (code "92") (name "unconnected-(U$1-Pad24)") (class "Default")
      (node (ref "U$1") (pin "24") (pinfunction "24_24") (pintype "passive"))
    )
    (net (code "93") (name "unconnected-(U$1-Pad25)") (class "Default")
      (node (ref "U$1") (pin "25") (pinfunction "25_25") (pintype "passive"))
    )
    (net (code "94") (name "unconnected-(U$1-Pad26)") (class "Default")
      (node (ref "U$1") (pin "26") (pinfunction "26_26") (pintype "passive"))
    )
    (net (code "95") (name "unconnected-(U$1-Pad27)") (class "Default")
      (node (ref "U$1") (pin "27") (pinfunction "27_27") (pintype "passive"))
    )
    (net (code "96") (name "unconnected-(U$1-Pad28)") (class "Default")
      (node (ref "U$1") (pin "28") (pinfunction "28_28") (pintype "passive"))
    )
    (net (code "97") (name "unconnected-(U$1-Pad29)") (class "Default")
      (node (ref "U$1") (pin "29") (pinfunction "29_29") (pintype "passive"))
    )
    (net (code "98") (name "unconnected-(U$1-Pad30)") (class "Default")
      (node (ref "U$1") (pin "30") (pinfunction "30_30") (pintype "passive"))
    )
    (net (code "99") (name "unconnected-(U$1-Pad31)") (class "Default")
      (node (ref "U$1") (pin "31") (pinfunction "31_31") (pintype "passive"))
    )
    (net (code "100") (name "unconnected-(U$1-Pad32)") (class "Default")
      (node (ref "U$1") (pin "32") (pinfunction "32_32") (pintype "passive"))
    )
    (net (code "101") (name "unconnected-(U$1-Pad33)") (class "Default")
      (node (ref "U$1") (pin "33") (pinfunction "33_33") (pintype "passive"))
    )
    (net (code "102") (name "unconnected-(U$1-Pad34)") (class "Default")
      (node (ref "U$1") (pin "34") (pinfunction "34_34") (pintype "passive"))
    )
    (net (code "103") (name "unconnected-(U$1-Pad35)") (class "Default")
      (node (ref "U$1") (pin "35") (pinfunction "35_35") (pintype "passive"))
    )
    (net (code "104") (name "unconnected-(U$1-Pad36)") (class "Default")
      (node (ref "U$1") (pin "36") (pinfunction "36_36") (pintype "passive"))
    )
    (net (code "105") (name "unconnected-(U$1-Pad37)") (class "Default")
      (node (ref "U$1") (pin "37") (pinfunction "37_37") (pintype "passive"))
    )
    (net (code "106") (name "unconnected-(U$1-Pad38)") (class "Default")
      (node (ref "U$1") (pin "38") (pinfunction "38_38") (pintype "passive"))
    )
    (net (code "107") (name "unconnected-(U$1-Pad39)") (class "Default")
      (node (ref "U$1") (pin "39") (pinfunction "39_39") (pintype "passive"))
    )
    (net (code "108") (name "unconnected-(U$1-Pad40)") (class "Default")
      (node (ref "U$1") (pin "40") (pinfunction "40_40") (pintype "passive"))
    )
    (net (code "109") (name "unconnected-(U$3-PB0(SS)-Pad8)") (class "Default")
      (node (ref "U$3") (pin "8") (pinfunction "PB0(SS)_8") (pintype "bidirectional"))
    )
    (net (code "110") (name "unconnected-(U$3-PB4(ADC11)-Pad28)") (class "Default")
      (node (ref "U$3") (pin "28") (pinfunction "PB4(ADC11)_28") (pintype "bidirectional"))
    )
    (net (code "111") (name "unconnected-(U$3-PD4(ICP1{slash}ADC8)-Pad25)") (class "Default")
      (node (ref "U$3") (pin "25") (pinfunction "PD4(ICP1/ADC8)_25") (pintype "bidirectional"))
    )
    (net (code "112") (name "unconnected-(U$3-PD5(XCK{slash}CTS)-Pad22)") (class "Default")
      (node (ref "U$3") (pin "22") (pinfunction "PD5(XCK/CTS)_22") (pintype "bidirectional"))
    )
    (net (code "113") (name "unconnected-(U$3-PD6(T1{slash}ADC9{slash}~{OC4D})-Pad26)") (class "Default")
      (node (ref "U$3") (pin "26") (pinfunction "PD6(T1/ADC9/~{OC4D})_26") (pintype "bidirectional"))
    )
    (net (code "114") (name "unconnected-(U$3-PD7(OC4D{slash}ADC10{slash}T0)-Pad27)") (class "Default")
      (node (ref "U$3") (pin "27") (pinfunction "PD7(OC4D/ADC10/T0)_27") (pintype "bidirectional"))
    )
    (net (code "115") (name "unconnected-(U$3-PE6(INT.6{slash}AIN0)-Pad1)") (class "Default")
      (node (ref "U$3") (pin "1") (pinfunction "PE6(INT.6/AIN0)_1") (pintype "bidirectional"))
    )
    (net (code "116") (name "unconnected-(U1-A0-Pad7)") (class "Default")
      (node (ref "U1") (pin "7") (pinfunction "A0_7") (pintype "input"))
    )
    (net (code "117") (name "unconnected-(U1-A1-Pad6)") (class "Default")
      (node (ref "U1") (pin "6") (pinfunction "A1_6") (pintype "input"))
    )
    (net (code "118") (name "unconnected-(U1-A2-Pad5)") (class "Default")
      (node (ref "U1") (pin "5") (pinfunction "A2_5") (pintype "input"))
    )
    (net (code "119") (name "unconnected-(U1-O.S.-Pad3)") (class "Default")
      (node (ref "U1") (pin "3") (pinfunction "O.S._3") (pintype "output"))
    )
    (net (code "120") (name "unconnected-(U4-A1-Pad2)") (class "Default")
      (node (ref "U4") (pin "2") (pinfunction "A1_2") (pintype "bidirectional"))
    )
    (net (code "121") (name "unconnected-(U4-A2-Pad3)") (class "Default")
      (node (ref "U4") (pin "3") (pinfunction "A2_3") (pintype "bidirectional"))
    )
    (net (code "122") (name "unconnected-(U4-A3-Pad4)") (class "Default")
      (node (ref "U4") (pin "4") (pinfunction "A3_4") (pintype "bidirectional"))
    )
    (net (code "123") (name "unconnected-(U4-A4-Pad5)") (class "Default")
      (node (ref "U4") (pin "5") (pinfunction "A4_5") (pintype "bidirectional"))
    )
    (net (code "124") (name "unconnected-(U4-B1-Pad13)") (class "Default")
      (node (ref "U4") (pin "13") (pinfunction "B1_13") (pintype "bidirectional"))
    )
    (net (code "125") (name "unconnected-(U4-B2-Pad12)") (class "Default")
      (node (ref "U4") (pin "12") (pinfunction "B2_12") (pintype "bidirectional"))
    )
    (net (code "126") (name "unconnected-(U4-B3-Pad11)") (class "Default")
      (node (ref "U4") (pin "11") (pinfunction "B3_11") (pintype "bidirectional"))
    )
    (net (code "127") (name "unconnected-(U4-B4-Pad10)") (class "Default")
      (node (ref "U4") (pin "10") (pinfunction "B4_10") (pintype "bidirectional"))
    )
    (net (code "128") (name "unconnected-(U4-GND-Pad7)") (class "Default")
      (node (ref "U4") (pin "7") (pinfunction "GND_7") (pintype "bidirectional"))
    )
    (net (code "129") (name "unconnected-(U4-OE-Pad8)") (class "Default")
      (node (ref "U4") (pin "8") (pinfunction "OE_8") (pintype "bidirectional"))
    )
    (net (code "130") (name "unconnected-(U4-VCCA-Pad1)") (class "Default")
      (node (ref "U4") (pin "1") (pinfunction "VCCA_1") (pintype "bidirectional"))
    )
    (net (code "131") (name "unconnected-(U4-VCCB-Pad14)") (class "Default")
      (node (ref "U4") (pin "14") (pinfunction "VCCB_14") (pintype "bidirectional"))
    )
    (net (code "132") (name "unconnected-(X2-Pad4)") (class "Default")
      (node (ref "X2") (pin "4") (pinfunction "4_4") (pintype "passive"))
    )
  )
)
